# Sheet2-USB.net
KiCad netlist of a schematic drawn in Altium Designer
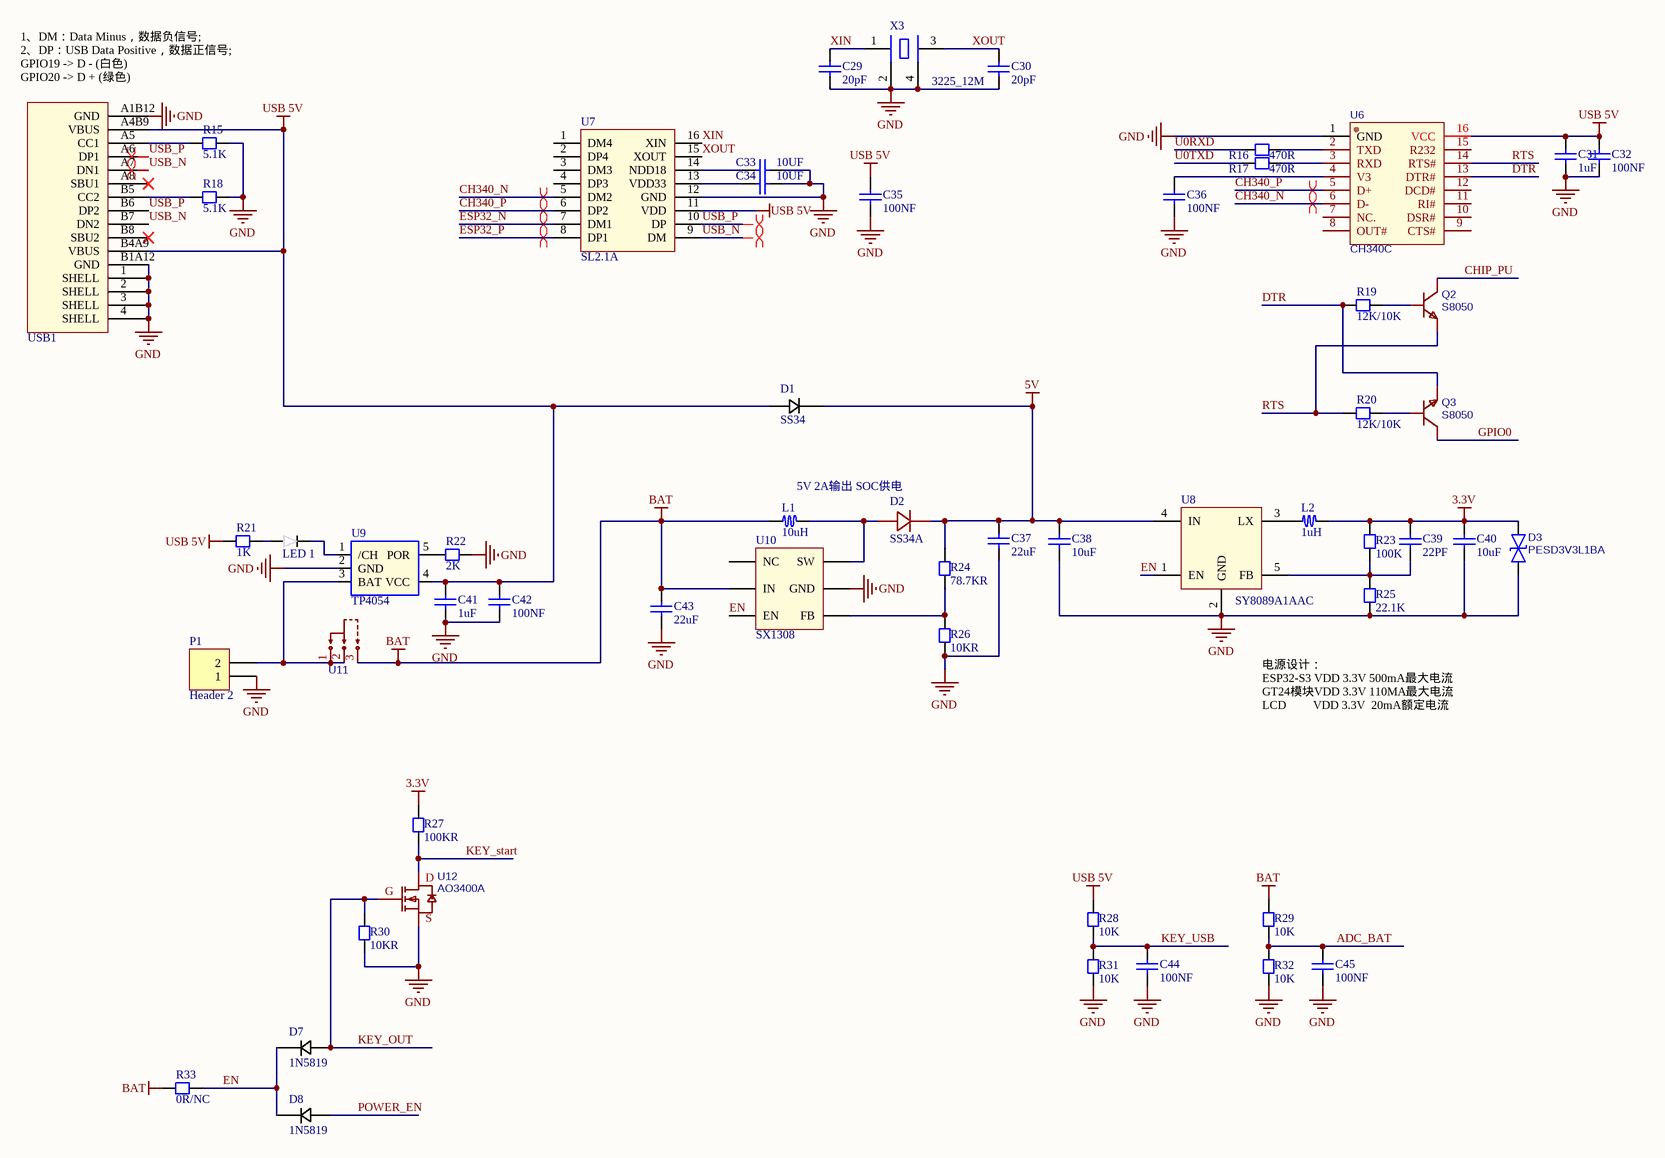
[diagram p0: Sheet2-USB.SchDoc]

(export (version "E")
  (design (tool "Eeschema 10.0.6"))
  (components
    (comp (ref "C29")
      (value "20pF")
      (footprint "CC1608-0603")
      (description "0603封装的电容")
      (fields (field (name "PUBLISHER") "Altium Limited"))
      (libsource (lib "base") (part "Cap Chip 0603"))
    )
    (comp (ref "C30")
      (value "20pF")
      (footprint "CC1608-0603")
      (description "0603封装的电容")
      (fields (field (name "PUBLISHER") "Altium Limited"))
      (libsource (lib "base") (part "Cap Chip 0603"))
    )
    (comp (ref "C31")
      (value "1uF")
      (footprint "CC1608-0603")
      (description "0603封装的电容")
      (fields (field (name "PUBLISHER") "Altium Limited"))
      (libsource (lib "base") (part "Cap Chip 0603"))
    )
    (comp (ref "C32")
      (value "100NF")
      (footprint "CC1608-0603")
      (description "0603封装的电容")
      (fields (field (name "PUBLISHER") "Altium Limited"))
      (libsource (lib "base") (part "Cap Chip 0603"))
    )
    (comp (ref "C33")
      (value "10UF")
      (footprint "CC1608-0603")
      (description "0603封装的电容")
      (fields (field (name "PUBLISHER") "Altium Limited"))
      (libsource (lib "base") (part "Cap Chip 0603"))
    )
    (comp (ref "C34")
      (value "10UF")
      (footprint "CC1608-0603")
      (description "0603封装的电容")
      (fields (field (name "PUBLISHER") "Altium Limited"))
      (libsource (lib "base") (part "Cap Chip 0603"))
    )
    (comp (ref "C35")
      (value "100NF")
      (footprint "CC1608-0603")
      (description "0603封装的电容")
      (fields (field (name "PUBLISHER") "Altium Limited"))
      (libsource (lib "base") (part "Cap Chip 0603"))
    )
    (comp (ref "C36")
      (value "100NF")
      (footprint "CC1608-0603")
      (description "0603封装的电容")
      (fields (field (name "PUBLISHER") "Altium Limited"))
      (libsource (lib "base") (part "Cap Chip 0603"))
    )
    (comp (ref "C37")
      (value "22uF")
      (footprint "CC1608-0603")
      (description "贴片电容")
      (libsource (lib "tianxiaohua_Schlib") (part "Chip capacitor"))
    )
    (comp (ref "C38")
      (value "10uF")
      (footprint "CC1608-0603")
      (description "0603封装的电容")
      (fields (field (name "PUBLISHER") "Altium Limited"))
      (libsource (lib "base") (part "Cap Chip 0603"))
    )
    (comp (ref "C39")
      (value "22PF")
      (footprint "CC1608-0603")
      (description "0603封装的电容")
      (fields (field (name "PUBLISHER") "Altium Limited"))
      (libsource (lib "base") (part "Cap Chip 0603"))
    )
    (comp (ref "C40")
      (value "10uF")
      (footprint "CC1608-0603")
      (description "0603封装的电容")
      (fields (field (name "PUBLISHER") "Altium Limited"))
      (libsource (lib "base") (part "Cap Chip 0603"))
    )
    (comp (ref "C41")
      (value "1uF")
      (footprint "CC1608-0603")
      (description "0603封装的电容")
      (fields (field (name "PUBLISHER") "Altium Limited"))
      (libsource (lib "base") (part "Cap Chip 0603"))
    )
    (comp (ref "C42")
      (value "100NF")
      (footprint "CC1608-0603")
      (description "0603封装的电容")
      (fields (field (name "PUBLISHER") "Altium Limited"))
      (libsource (lib "base") (part "Cap Chip 0603"))
    )
    (comp (ref "C43")
      (value "22uF")
      (footprint "CC1608-0603")
      (description "0603封装的电容")
      (fields (field (name "PUBLISHER") "Altium Limited"))
      (libsource (lib "base") (part "Cap Chip 0603"))
    )
    (comp (ref "C44")
      (value "100NF")
      (footprint "CC1608-0603")
      (description "0603封装的电容")
      (fields (field (name "PUBLISHER") "Altium Limited"))
      (libsource (lib "base") (part "Cap Chip 0603"))
    )
    (comp (ref "C45")
      (value "100NF")
      (footprint "CC1608-0603")
      (description "0603封装的电容")
      (fields (field (name "PUBLISHER") "Altium Limited"))
      (libsource (lib "base") (part "Cap Chip 0603"))
    )
    (comp (ref "D1")
      (value "SS34")
      (footprint "DO-214 AA")
      (description "肖特基二极管")
      (libsource (lib "transistor") (part "SS34"))
    )
    (comp (ref "D2")
      (value "SS34A")
      (footprint "DO-214 AA SMB")
      (description "大电流肖特基二极管，5A/40V")
      (libsource (lib "tianxiaohua_Schlib") (part "SS34A"))
    )
    (comp (ref "D3")
      (value "PESD3V3L1BA")
      (footprint "SOD-323")
      (description "SOD-323 3.3V 双向ESD防静电二极管保护芯片")
      (fields (field (name "MANUFACTURER") "MDD") (field (name "MANUFACTURER PART") "SMAJ6.5CA"))
      (libsource (lib "transistor") (part "PESD3V3L1BA"))
    )
    (comp (ref "D7")
      (value "1N5819")
      (footprint "SOD-323_L1.8-W1.3-LS2.5-RD")
      (description "肖特基二极管")
      (libsource (lib "transistor") (part "1N5819"))
    )
    (comp (ref "D8")
      (value "1N5819")
      (footprint "SOD-323_L1.8-W1.3-LS2.5-RD")
      (description "肖特基二极管")
      (libsource (lib "transistor") (part "1N5819"))
    )
    (comp (ref "L1")
      (value "10uH")
      (footprint "Inductor-6045")
      (description "6045封装 线绕SMD功率电感")
      (libsource (lib "base") (part "Inductor-6045"))
    )
    (comp (ref "L2")
      (value "1uH")
      (footprint "Inductor-4018")
      (description "贴片电感 1206封装")
      (libsource (lib "base") (part "Inductor-4018"))
    )
    (comp (ref "LED 1") (value "LED 0603") (footprint "LED 0603") (libsource (lib "base") (part "LED 0603")))
    (comp (ref "P1")
      (value "Header 2")
      (footprint "HX2.54-2")
      (description "Header, 2-Pin")
      (fields (field (name "PUBLISHER") "Altium Limited"))
      (libsource (lib "Connectors") (part "Header 2"))
    )
    (comp (ref "Q2")
      (value "S8050")
      (footprint "SOT-23")
      (fields (field (name "MANUFACTURER") "SALLTECH(萨瑞)") (field (name "CONTRIBUTOR") "lcsc"))
      (libsource (lib "transistor") (part "S8050"))
    )
    (comp (ref "Q3")
      (value "S8050")
      (footprint "SOT-23")
      (fields (field (name "MANUFACTURER") "SALLTECH(萨瑞)") (field (name "CONTRIBUTOR") "lcsc"))
      (libsource (lib "transistor") (part "S8050"))
    )
    (comp (ref "R15")
      (value "5.1K")
      (footprint "CR1608-0603")
      (description "0603封装电阻")
      (fields (field (name "PUBLISHER") "Altium Limited"))
      (libsource (lib "") (part "Resistor Chip 0603_3"))
    )
    (comp (ref "R16")
      (value "470R")
      (footprint "CR1608-0603")
      (description "0603封装电阻")
      (fields (field (name "PUBLISHER") "Altium Limited"))
      (libsource (lib "") (part "Resistor Chip 0603_3"))
    )
    (comp (ref "R17")
      (value "470R")
      (footprint "CR1608-0603")
      (description "0603封装电阻")
      (fields (field (name "PUBLISHER") "Altium Limited"))
      (libsource (lib "") (part "Resistor Chip 0603_3"))
    )
    (comp (ref "R18")
      (value "5.1K")
      (footprint "CR1608-0603")
      (description "0603封装电阻")
      (fields (field (name "PUBLISHER") "Altium Limited"))
      (libsource (lib "") (part "Resistor Chip 0603_3"))
    )
    (comp (ref "R19")
      (value "12K/10K")
      (footprint "CR1608-0603")
      (description "0603封装电阻")
      (fields (field (name "PUBLISHER") "Altium Limited"))
      (libsource (lib "base") (part "Resistor Chip 0603"))
    )
    (comp (ref "R20")
      (value "12K/10K")
      (footprint "CR1608-0603")
      (description "0603封装电阻")
      (fields (field (name "PUBLISHER") "Altium Limited"))
      (libsource (lib "") (part "Resistor Chip 0603_2"))
    )
    (comp (ref "R21")
      (value "1K")
      (footprint "CR1608-0603")
      (description "0603封装电阻")
      (fields (field (name "PUBLISHER") "Altium Limited"))
      (libsource (lib "base") (part "Resistor Chip 0603"))
    )
    (comp (ref "R22")
      (value "2K")
      (footprint "CR1608-0603")
      (description "0603封装电阻")
      (fields (field (name "PUBLISHER") "Altium Limited"))
      (libsource (lib "base") (part "Resistor Chip 0603"))
    )
    (comp (ref "R23")
      (value "100K")
      (footprint "CR1608-0603")
      (description "0603封装电阻")
      (fields (field (name "PUBLISHER") "Altium Limited"))
      (libsource (lib "") (part "Resistor Chip 0603_1"))
    )
    (comp (ref "R24")
      (value "78.7KR")
      (footprint "CR1608-0603")
      (description "贴片电阻")
      (libsource (lib "tianxiaohua_Schlib") (part "Chip resistor"))
    )
    (comp (ref "R25")
      (value "22.1K")
      (footprint "CR1608-0603")
      (description "0603封装电阻")
      (fields (field (name "PUBLISHER") "Altium Limited"))
      (libsource (lib "") (part "Resistor Chip 0603_1"))
    )
    (comp (ref "R26")
      (value "10KR")
      (footprint "CR1608-0603")
      (description "贴片电阻")
      (libsource (lib "tianxiaohua_Schlib") (part "Chip resistor"))
    )
    (comp (ref "R27")
      (value "100KR")
      (footprint "CR1608-0603")
      (description "贴片电阻")
      (libsource (lib "tianxiaohua_Schlib") (part "Chip resistor"))
    )
    (comp (ref "R28")
      (value "10K")
      (footprint "CR1608-0603")
      (description "0603封装电阻")
      (fields (field (name "PUBLISHER") "Altium Limited"))
      (libsource (lib "") (part "Resistor Chip 0603_2"))
    )
    (comp (ref "R29")
      (value "10K")
      (footprint "CR1608-0603")
      (description "0603封装电阻")
      (fields (field (name "PUBLISHER") "Altium Limited"))
      (libsource (lib "") (part "Resistor Chip 0603_2"))
    )
    (comp (ref "R30")
      (value "10KR")
      (footprint "CR1608-0603")
      (description "贴片电阻")
      (libsource (lib "tianxiaohua_Schlib") (part "Chip resistor"))
    )
    (comp (ref "R31")
      (value "10K")
      (footprint "CR1608-0603")
      (description "0603封装电阻")
      (fields (field (name "PUBLISHER") "Altium Limited"))
      (libsource (lib "") (part "Resistor Chip 0603_2"))
    )
    (comp (ref "R32")
      (value "10K")
      (footprint "CR1608-0603")
      (description "0603封装电阻")
      (fields (field (name "PUBLISHER") "Altium Limited"))
      (libsource (lib "") (part "Resistor Chip 0603_2"))
    )
    (comp (ref "R33")
      (value "0R/NC")
      (footprint "CR1608-0603")
      (description "0603封装电阻")
      (fields (field (name "PUBLISHER") "Altium Limited"))
      (libsource (lib "base") (part "Resistor Chip 0603"))
    )
    (comp (ref "U6")
      (value "CH340C")
      (footprint "SOP-16")
      (fields (field (name "MANUFACTURER") "WCH(南京沁恒)"))
      (libsource (lib "PB-Chip") (part "CH340C"))
    )
    (comp (ref "U7")
      (value "SL2.1A")
      (footprint "SOP-16")
      (description "USB HUB 四拓展")
      (libsource (lib "sensor") (part "SL2.1A"))
    )
    (comp (ref "U8")
      (value "SY8089A1AAC")
      (footprint "SOT23-5")
      (libsource (lib "power-chip") (part "SY8089A1AAC"))
    )
    (comp (ref "U9")
      (value "TP4054")
      (footprint "SOT23-5")
      (description "迷你充电IC SOT-23-5")
      (libsource (lib "power-chip") (part "TP4054"))
    )
    (comp (ref "U10")
      (value "SX1308")
      (footprint "SOT23-6")
      (description "SOT23-6 升压芯片")
      (libsource (lib "power-chip") (part "SX1308"))
    )
    (comp (ref "U11")
      (value "HX SS12D10G4")
      (footprint "SW-TH_3P-SS12D06")
      (fields (field (name "BOM_SUPPLIER PART") "C5149841") (field (name "CONTRIBUTOR") "lcsc"))
      (libsource (lib "base") (part "SW-TH_3P-SS12D06"))
    )
    (comp (ref "U12")
      (value "AO3400A")
      (footprint "SOT-23")
      (description "UMW AO3400A SOT-23 30V/5.8A N沟道 MOS(场效应管)芯片")
      (fields
        (field (name "MANUFACTURER") "ElecSuper(静芯微）")
        (field (name "MANUFACTURER PART") "AO3401A")
        (field (name "CONTRIBUTOR") "lcsc")
      )
      (libsource (lib "transistor") (part "AO3400A"))
    )
    (comp (ref "USB1")
      (value "Tpye-c 16P")
      (footprint "TYPE-C 16P")
      (description "16P 封装的TYPE -c接口 4固定插脚 双向")
      (libsource (lib "Connectors") (part "Tpye-c 16P"))
    )
    (comp (ref "X3")
      (value "3225_12M")
      (footprint "XTAL-3225")
      (description "3225封装的晶振")
      (libsource (lib "base") (part "XTAL 3225"))
    )
  )
  (nets
    (net (code "1") (name "/ADC_BAT") (class "Default")
      (node (ref "C45") (pin "2") (pinfunction "2_2") (pintype "passive"))
      (node (ref "R29") (pin "1") (pinfunction "1_1") (pintype "passive"))
      (node (ref "R32") (pin "2") (pinfunction "2_2") (pintype "passive"))
    )
    (net (code "2") (name "/CH340_N") (class "Default")
      (node (ref "U6") (pin "6") (pinfunction "D-_6") (pintype "passive"))
      (node (ref "U7") (pin "5") (pinfunction "DM2_5") (pintype "passive"))
    )
    (net (code "3") (name "/CH340_P") (class "Default")
      (node (ref "U6") (pin "5") (pinfunction "D+_5") (pintype "passive"))
      (node (ref "U7") (pin "6") (pinfunction "DP2_6") (pintype "passive"))
    )
    (net (code "4") (name "/CHIP_PU") (class "Default")
      (node (ref "Q2") (pin "3") (pinfunction "C_3") (pintype "passive"))
    )
    (net (code "5") (name "/DTR") (class "Default")
      (node (ref "Q3") (pin "2") (pinfunction "E_2") (pintype "passive"))
      (node (ref "R19") (pin "1") (pinfunction "1_1") (pintype "passive"))
      (node (ref "U6") (pin "13") (pinfunction "DTR#_13") (pintype "passive"))
    )
    (net (code "6") (name "/EN") (class "Default")
      (node (ref "D7") (pin "1") (pinfunction "1_1") (pintype "passive"))
      (node (ref "D8") (pin "1") (pinfunction "1_1") (pintype "passive"))
      (node (ref "R33") (pin "2") (pinfunction "2_2") (pintype "passive"))
      (node (ref "U10") (pin "4") (pinfunction "EN_4") (pintype "passive"))
      (node (ref "U8") (pin "1") (pinfunction "EN_1") (pintype "passive"))
    )
    (net (code "7") (name "/ESP32_N") (class "Default")
      (node (ref "U7") (pin "7") (pinfunction "DM1_7") (pintype "passive"))
    )
    (net (code "8") (name "/ESP32_P") (class "Default")
      (node (ref "U7") (pin "8") (pinfunction "DP1_8") (pintype "passive"))
    )
    (net (code "9") (name "/GPIO0") (class "Default")
      (node (ref "Q3") (pin "3") (pinfunction "C_3") (pintype "passive"))
    )
    (net (code "10") (name "/KEY_OUT") (class "Default")
      (node (ref "D7") (pin "2") (pinfunction "2_2") (pintype "passive"))
      (node (ref "R30") (pin "2") (pinfunction "2_2") (pintype "passive"))
      (node (ref "U12") (pin "1") (pinfunction "G_1") (pintype "passive"))
    )
    (net (code "11") (name "/KEY_USB") (class "Default")
      (node (ref "C44") (pin "2") (pinfunction "2_2") (pintype "passive"))
      (node (ref "R28") (pin "1") (pinfunction "1_1") (pintype "passive"))
      (node (ref "R31") (pin "2") (pinfunction "2_2") (pintype "passive"))
    )
    (net (code "12") (name "/KEY_start") (class "Default")
      (node (ref "R27") (pin "1") (pinfunction "1_1") (pintype "passive"))
      (node (ref "U12") (pin "3") (pinfunction "D_3") (pintype "passive"))
    )
    (net (code "13") (name "/POWER_EN") (class "Default")
      (node (ref "D8") (pin "2") (pinfunction "2_2") (pintype "passive"))
    )
    (net (code "14") (name "/RTS") (class "Default")
      (node (ref "Q2") (pin "2") (pinfunction "E_2") (pintype "passive"))
      (node (ref "R20") (pin "1") (pinfunction "1_1") (pintype "passive"))
      (node (ref "U6") (pin "14") (pinfunction "RTS#_14") (pintype "passive"))
    )
    (net (code "15") (name "/U0RXD") (class "Default")
      (node (ref "R16") (pin "2") (pinfunction "2_2") (pintype "passive"))
    )
    (net (code "16") (name "/U0TXD") (class "Default")
      (node (ref "R17") (pin "2") (pinfunction "2_2") (pintype "passive"))
    )
    (net (code "17") (name "/USB_N") (class "Default")
      (node (ref "U7") (pin "9") (pinfunction "DM_9") (pintype "passive"))
      (node (ref "USB1") (pin "A7") (pinfunction "DN1_A7") (pintype "power_in"))
      (node (ref "USB1") (pin "B7") (pinfunction "DN2_B7") (pintype "power_in"))
    )
    (net (code "18") (name "/USB_P") (class "Default")
      (node (ref "U7") (pin "10") (pinfunction "DP_10") (pintype "passive"))
      (node (ref "USB1") (pin "A6") (pinfunction "DP1_A6") (pintype "power_in"))
      (node (ref "USB1") (pin "B6") (pinfunction "DP2_B6") (pintype "power_in"))
    )
    (net (code "19") (name "/XIN") (class "Default")
      (node (ref "C29") (pin "2") (pinfunction "2_2") (pintype "passive"))
      (node (ref "U7") (pin "16") (pinfunction "XIN_16") (pintype "passive"))
      (node (ref "X3") (pin "1") (pinfunction "OSC1_1") (pintype "passive"))
    )
    (net (code "20") (name "/XOUT") (class "Default")
      (node (ref "C30") (pin "2") (pinfunction "2_2") (pintype "passive"))
      (node (ref "U7") (pin "15") (pinfunction "XOUT_15") (pintype "passive"))
      (node (ref "X3") (pin "3") (pinfunction "OSC2_3") (pintype "passive"))
    )
    (net (code "21") (name "3.3V") (class "Default")
      (node (ref "C39") (pin "2") (pinfunction "2_2") (pintype "passive"))
      (node (ref "C40") (pin "2") (pinfunction "2_2") (pintype "passive"))
      (node (ref "D3") (pin "1") (pinfunction "1_1") (pintype "passive"))
      (node (ref "L2") (pin "2") (pinfunction "2_2") (pintype "passive"))
      (node (ref "R23") (pin "1") (pinfunction "1_1") (pintype "passive"))
      (node (ref "R27") (pin "2") (pinfunction "2_2") (pintype "passive"))
    )
    (net (code "22") (name "5V") (class "Default")
      (node (ref "C37") (pin "1") (pinfunction "1_1") (pintype "passive"))
      (node (ref "C38") (pin "2") (pinfunction "2_2") (pintype "passive"))
      (node (ref "D1") (pin "1") (pinfunction "K_1") (pintype "passive"))
      (node (ref "D2") (pin "1") (pinfunction "C_1") (pintype "passive"))
      (node (ref "R24") (pin "2") (pinfunction "2_2") (pintype "passive"))
      (node (ref "U8") (pin "4") (pinfunction "IN_4") (pintype "passive"))
    )
    (net (code "23") (name "BAT") (class "Default")
      (node (ref "C43") (pin "2") (pinfunction "2_2") (pintype "passive"))
      (node (ref "L1") (pin "1") (pinfunction "1_1") (pintype "passive"))
      (node (ref "R29") (pin "2") (pinfunction "2_2") (pintype "passive"))
      (node (ref "R33") (pin "1") (pinfunction "1_1") (pintype "passive"))
      (node (ref "U10") (pin "5") (pinfunction "IN_5") (pintype "passive"))
      (node (ref "U11") (pin "3") (pinfunction "3_3") (pintype "passive"))
    )
    (net (code "24") (name "GND") (class "Default")
      (node (ref "C29") (pin "1") (pinfunction "1_1") (pintype "passive"))
      (node (ref "C30") (pin "1") (pinfunction "1_1") (pintype "passive"))
      (node (ref "C31") (pin "1") (pinfunction "1_1") (pintype "passive"))
      (node (ref "C32") (pin "1") (pinfunction "1_1") (pintype "passive"))
      (node (ref "C33") (pin "1") (pinfunction "1_1") (pintype "passive"))
      (node (ref "C34") (pin "1") (pinfunction "1_1") (pintype "passive"))
      (node (ref "C35") (pin "1") (pinfunction "1_1") (pintype "passive"))
      (node (ref "C36") (pin "1") (pinfunction "1_1") (pintype "passive"))
      (node (ref "C37") (pin "2") (pinfunction "2_2") (pintype "passive"))
      (node (ref "C38") (pin "1") (pinfunction "1_1") (pintype "passive"))
      (node (ref "C40") (pin "1") (pinfunction "1_1") (pintype "passive"))
      (node (ref "C41") (pin "1") (pinfunction "1_1") (pintype "passive"))
      (node (ref "C42") (pin "1") (pinfunction "1_1") (pintype "passive"))
      (node (ref "C43") (pin "1") (pinfunction "1_1") (pintype "passive"))
      (node (ref "C44") (pin "1") (pinfunction "1_1") (pintype "passive"))
      (node (ref "C45") (pin "1") (pinfunction "1_1") (pintype "passive"))
      (node (ref "D3") (pin "2") (pinfunction "2_2") (pintype "passive"))
      (node (ref "P1") (pin "1") (pinfunction "1_1") (pintype "passive"))
      (node (ref "R15") (pin "1") (pinfunction "1_1") (pintype "passive"))
      (node (ref "R18") (pin "1") (pinfunction "1_1") (pintype "passive"))
      (node (ref "R22") (pin "2") (pinfunction "2_2") (pintype "passive"))
      (node (ref "R25") (pin "2") (pinfunction "2_2") (pintype "passive"))
      (node (ref "R26") (pin "1") (pinfunction "1_1") (pintype "passive"))
      (node (ref "R30") (pin "1") (pinfunction "1_1") (pintype "passive"))
      (node (ref "R31") (pin "1") (pinfunction "1_1") (pintype "passive"))
      (node (ref "R32") (pin "1") (pinfunction "1_1") (pintype "passive"))
      (node (ref "U10") (pin "2") (pinfunction "GND_2") (pintype "passive"))
      (node (ref "U12") (pin "2") (pinfunction "S_2") (pintype "passive"))
      (node (ref "U6") (pin "1") (pinfunction "GND_1") (pintype "passive"))
      (node (ref "U7") (pin "12") (pinfunction "GND_12") (pintype "passive"))
      (node (ref "U8") (pin "2") (pinfunction "GND_2") (pintype "passive"))
      (node (ref "U9") (pin "2") (pinfunction "GND_2") (pintype "passive"))
      (node (ref "USB1") (pin "1") (pinfunction "SHELL_1") (pintype "power_in"))
      (node (ref "USB1") (pin "2") (pinfunction "SHELL_2") (pintype "power_in"))
      (node (ref "USB1") (pin "3") (pinfunction "SHELL_3") (pintype "power_in"))
      (node (ref "USB1") (pin "4") (pinfunction "SHELL_4") (pintype "power_in"))
      (node (ref "USB1") (pin "A1B12") (pinfunction "GND_A1B12") (pintype "power_in"))
      (node (ref "USB1") (pin "B1A12") (pinfunction "GND_B1A12") (pintype "power_in"))
      (node (ref "X3") (pin "2") (pinfunction "GND_2") (pintype "passive"))
      (node (ref "X3") (pin "4") (pinfunction "GND_4") (pintype "passive"))
    )
    (net (code "25") (name "Net-(D2-A)") (class "Default")
      (node (ref "D2") (pin "2") (pinfunction "A_2") (pintype "passive"))
      (node (ref "L1") (pin "2") (pinfunction "2_2") (pintype "passive"))
      (node (ref "U10") (pin "1") (pinfunction "SW_1") (pintype "passive"))
    )
    (net (code "26") (name "Net-(LED 1-Pad1)") (class "Default")
      (node (ref "LED 1") (pin "1") (pinfunction "1_1") (pintype "passive"))
      (node (ref "R21") (pin "2") (pinfunction "2_2") (pintype "passive"))
    )
    (net (code "27") (name "Net-(Q2-B)") (class "Default")
      (node (ref "Q2") (pin "1") (pinfunction "B_1") (pintype "passive"))
      (node (ref "R19") (pin "2") (pinfunction "2_2") (pintype "passive"))
    )
    (net (code "28") (name "Net-(Q3-B)") (class "Default")
      (node (ref "Q3") (pin "1") (pinfunction "B_1") (pintype "passive"))
      (node (ref "R20") (pin "2") (pinfunction "2_2") (pintype "passive"))
    )
    (net (code "29") (name "Net-(U6-RXD)") (class "Default")
      (node (ref "R17") (pin "1") (pinfunction "1_1") (pintype "passive"))
      (node (ref "U6") (pin "3") (pinfunction "RXD_3") (pintype "passive"))
    )
    (net (code "30") (name "Net-(U6-TXD)") (class "Default")
      (node (ref "R16") (pin "1") (pinfunction "1_1") (pintype "passive"))
      (node (ref "U6") (pin "2") (pinfunction "TXD_2") (pintype "passive"))
    )
    (net (code "31") (name "Net-(U6-V3)") (class "Default")
      (node (ref "C36") (pin "2") (pinfunction "2_2") (pintype "passive"))
      (node (ref "U6") (pin "4") (pinfunction "V3_4") (pintype "passive"))
    )
    (net (code "32") (name "Net-(U7-NDD18)") (class "Default")
      (node (ref "C33") (pin "2") (pinfunction "2_2") (pintype "passive"))
      (node (ref "U7") (pin "14") (pinfunction "NDD18_14") (pintype "passive"))
    )
    (net (code "33") (name "Net-(U7-VDD33)") (class "Default")
      (node (ref "C34") (pin "2") (pinfunction "2_2") (pintype "passive"))
      (node (ref "U7") (pin "13") (pinfunction "VDD33_13") (pintype "passive"))
    )
    (net (code "34") (name "Net-(U8-FB)") (class "Default")
      (node (ref "C39") (pin "1") (pinfunction "1_1") (pintype "passive"))
      (node (ref "R23") (pin "2") (pinfunction "2_2") (pintype "passive"))
      (node (ref "R25") (pin "1") (pinfunction "1_1") (pintype "passive"))
      (node (ref "U8") (pin "5") (pinfunction "FB_5") (pintype "passive"))
    )
    (net (code "35") (name "Net-(U8-LX)") (class "Default")
      (node (ref "L2") (pin "1") (pinfunction "1_1") (pintype "passive"))
      (node (ref "U8") (pin "3") (pinfunction "LX_3") (pintype "passive"))
    )
    (net (code "36") (name "Net-(U9-BAT)") (class "Default")
      (node (ref "P1") (pin "2") (pinfunction "2_2") (pintype "passive"))
      (node (ref "U11") (pin "1") (pinfunction "1_1") (pintype "passive"))
      (node (ref "U11") (pin "2") (pinfunction "2_2") (pintype "passive"))
      (node (ref "U9") (pin "3") (pinfunction "BAT_3") (pintype "passive"))
    )
    (net (code "37") (name "Net-(U9-POR)") (class "Default")
      (node (ref "R22") (pin "1") (pinfunction "1_1") (pintype "passive"))
      (node (ref "U9") (pin "5") (pinfunction "POR_5") (pintype "passive"))
    )
    (net (code "38") (name "Net-(U9-{slash}CH)") (class "Default")
      (node (ref "LED 1") (pin "2") (pinfunction "2_2") (pintype "passive"))
      (node (ref "U9") (pin "1") (pinfunction "/CH_1") (pintype "passive"))
    )
    (net (code "39") (name "Net-(U10-FB)") (class "Default")
      (node (ref "R24") (pin "1") (pinfunction "1_1") (pintype "passive"))
      (node (ref "R26") (pin "2") (pinfunction "2_2") (pintype "passive"))
      (node (ref "U10") (pin "3") (pinfunction "FB_3") (pintype "passive"))
    )
    (net (code "40") (name "Net-(USB1-CC1)") (class "Default")
      (node (ref "R15") (pin "2") (pinfunction "2_2") (pintype "passive"))
      (node (ref "USB1") (pin "A5") (pinfunction "CC1_A5") (pintype "power_in"))
    )
    (net (code "41") (name "Net-(USB1-CC2)") (class "Default")
      (node (ref "R18") (pin "2") (pinfunction "2_2") (pintype "passive"))
      (node (ref "USB1") (pin "B5") (pinfunction "CC2_B5") (pintype "power_in"))
    )
    (net (code "42") (name "USB 5V") (class "Default")
      (node (ref "C31") (pin "2") (pinfunction "2_2") (pintype "passive"))
      (node (ref "C32") (pin "2") (pinfunction "2_2") (pintype "passive"))
      (node (ref "C35") (pin "2") (pinfunction "2_2") (pintype "passive"))
      (node (ref "C41") (pin "2") (pinfunction "2_2") (pintype "passive"))
      (node (ref "C42") (pin "2") (pinfunction "2_2") (pintype "passive"))
      (node (ref "D1") (pin "2") (pinfunction "A_2") (pintype "passive"))
      (node (ref "R21") (pin "1") (pinfunction "1_1") (pintype "passive"))
      (node (ref "R28") (pin "2") (pinfunction "2_2") (pintype "passive"))
      (node (ref "U6") (pin "16") (pinfunction "VCC_16") (pintype "passive"))
      (node (ref "U7") (pin "11") (pinfunction "VDD_11") (pintype "passive"))
      (node (ref "U9") (pin "4") (pinfunction "VCC_4") (pintype "passive"))
      (node (ref "USB1") (pin "A4B9") (pinfunction "VBUS_A4B9") (pintype "power_in"))
      (node (ref "USB1") (pin "B4A9") (pinfunction "VBUS_B4A9") (pintype "power_in"))
    )
    (net (code "43") (name "unconnected-(U6-CTS#-Pad9)") (class "Default")
      (node (ref "U6") (pin "9") (pinfunction "CTS#_9") (pintype "passive"))
    )
    (net (code "44") (name "unconnected-(U6-DCD#-Pad12)") (class "Default")
      (node (ref "U6") (pin "12") (pinfunction "DCD#_12") (pintype "passive"))
    )
    (net (code "45") (name "unconnected-(U6-DSR#-Pad10)") (class "Default")
      (node (ref "U6") (pin "10") (pinfunction "DSR#_10") (pintype "passive"))
    )
    (net (code "46") (name "unconnected-(U6-NC.-Pad7)") (class "Default")
      (node (ref "U6") (pin "7") (pinfunction "NC._7") (pintype "passive"))
    )
    (net (code "47") (name "unconnected-(U6-OUT#-Pad8)") (class "Default")
      (node (ref "U6") (pin "8") (pinfunction "OUT#_8") (pintype "passive"))
    )
    (net (code "48") (name "unconnected-(U6-R232-Pad15)") (class "Default")
      (node (ref "U6") (pin "15") (pinfunction "R232_15") (pintype "passive"))
    )
    (net (code "49") (name "unconnected-(U6-RI#-Pad11)") (class "Default")
      (node (ref "U6") (pin "11") (pinfunction "RI#_11") (pintype "passive"))
    )
    (net (code "50") (name "unconnected-(U7-DM3-Pad3)") (class "Default")
      (node (ref "U7") (pin "3") (pinfunction "DM3_3") (pintype "passive"))
    )
    (net (code "51") (name "unconnected-(U7-DM4-Pad1)") (class "Default")
      (node (ref "U7") (pin "1") (pinfunction "DM4_1") (pintype "passive"))
    )
    (net (code "52") (name "unconnected-(U7-DP3-Pad4)") (class "Default")
      (node (ref "U7") (pin "4") (pinfunction "DP3_4") (pintype "passive"))
    )
    (net (code "53") (name "unconnected-(U7-DP4-Pad2)") (class "Default")
      (node (ref "U7") (pin "2") (pinfunction "DP4_2") (pintype "passive"))
    )
    (net (code "54") (name "unconnected-(U10-NC-Pad6)") (class "Default")
      (node (ref "U10") (pin "6") (pinfunction "NC_6") (pintype "passive"))
    )
    (net (code "55") (name "unconnected-(USB1-SBU1-PadA8)") (class "Default")
      (node (ref "USB1") (pin "A8") (pinfunction "SBU1_A8") (pintype "power_in+no_connect"))
    )
    (net (code "56") (name "unconnected-(USB1-SBU2-PadB8)") (class "Default")
      (node (ref "USB1") (pin "B8") (pinfunction "SBU2_B8") (pintype "power_in+no_connect"))
    )
  )
)
